# PIC_closed_loop.net
KiCad netlist of a schematic drawn in Altium Designer
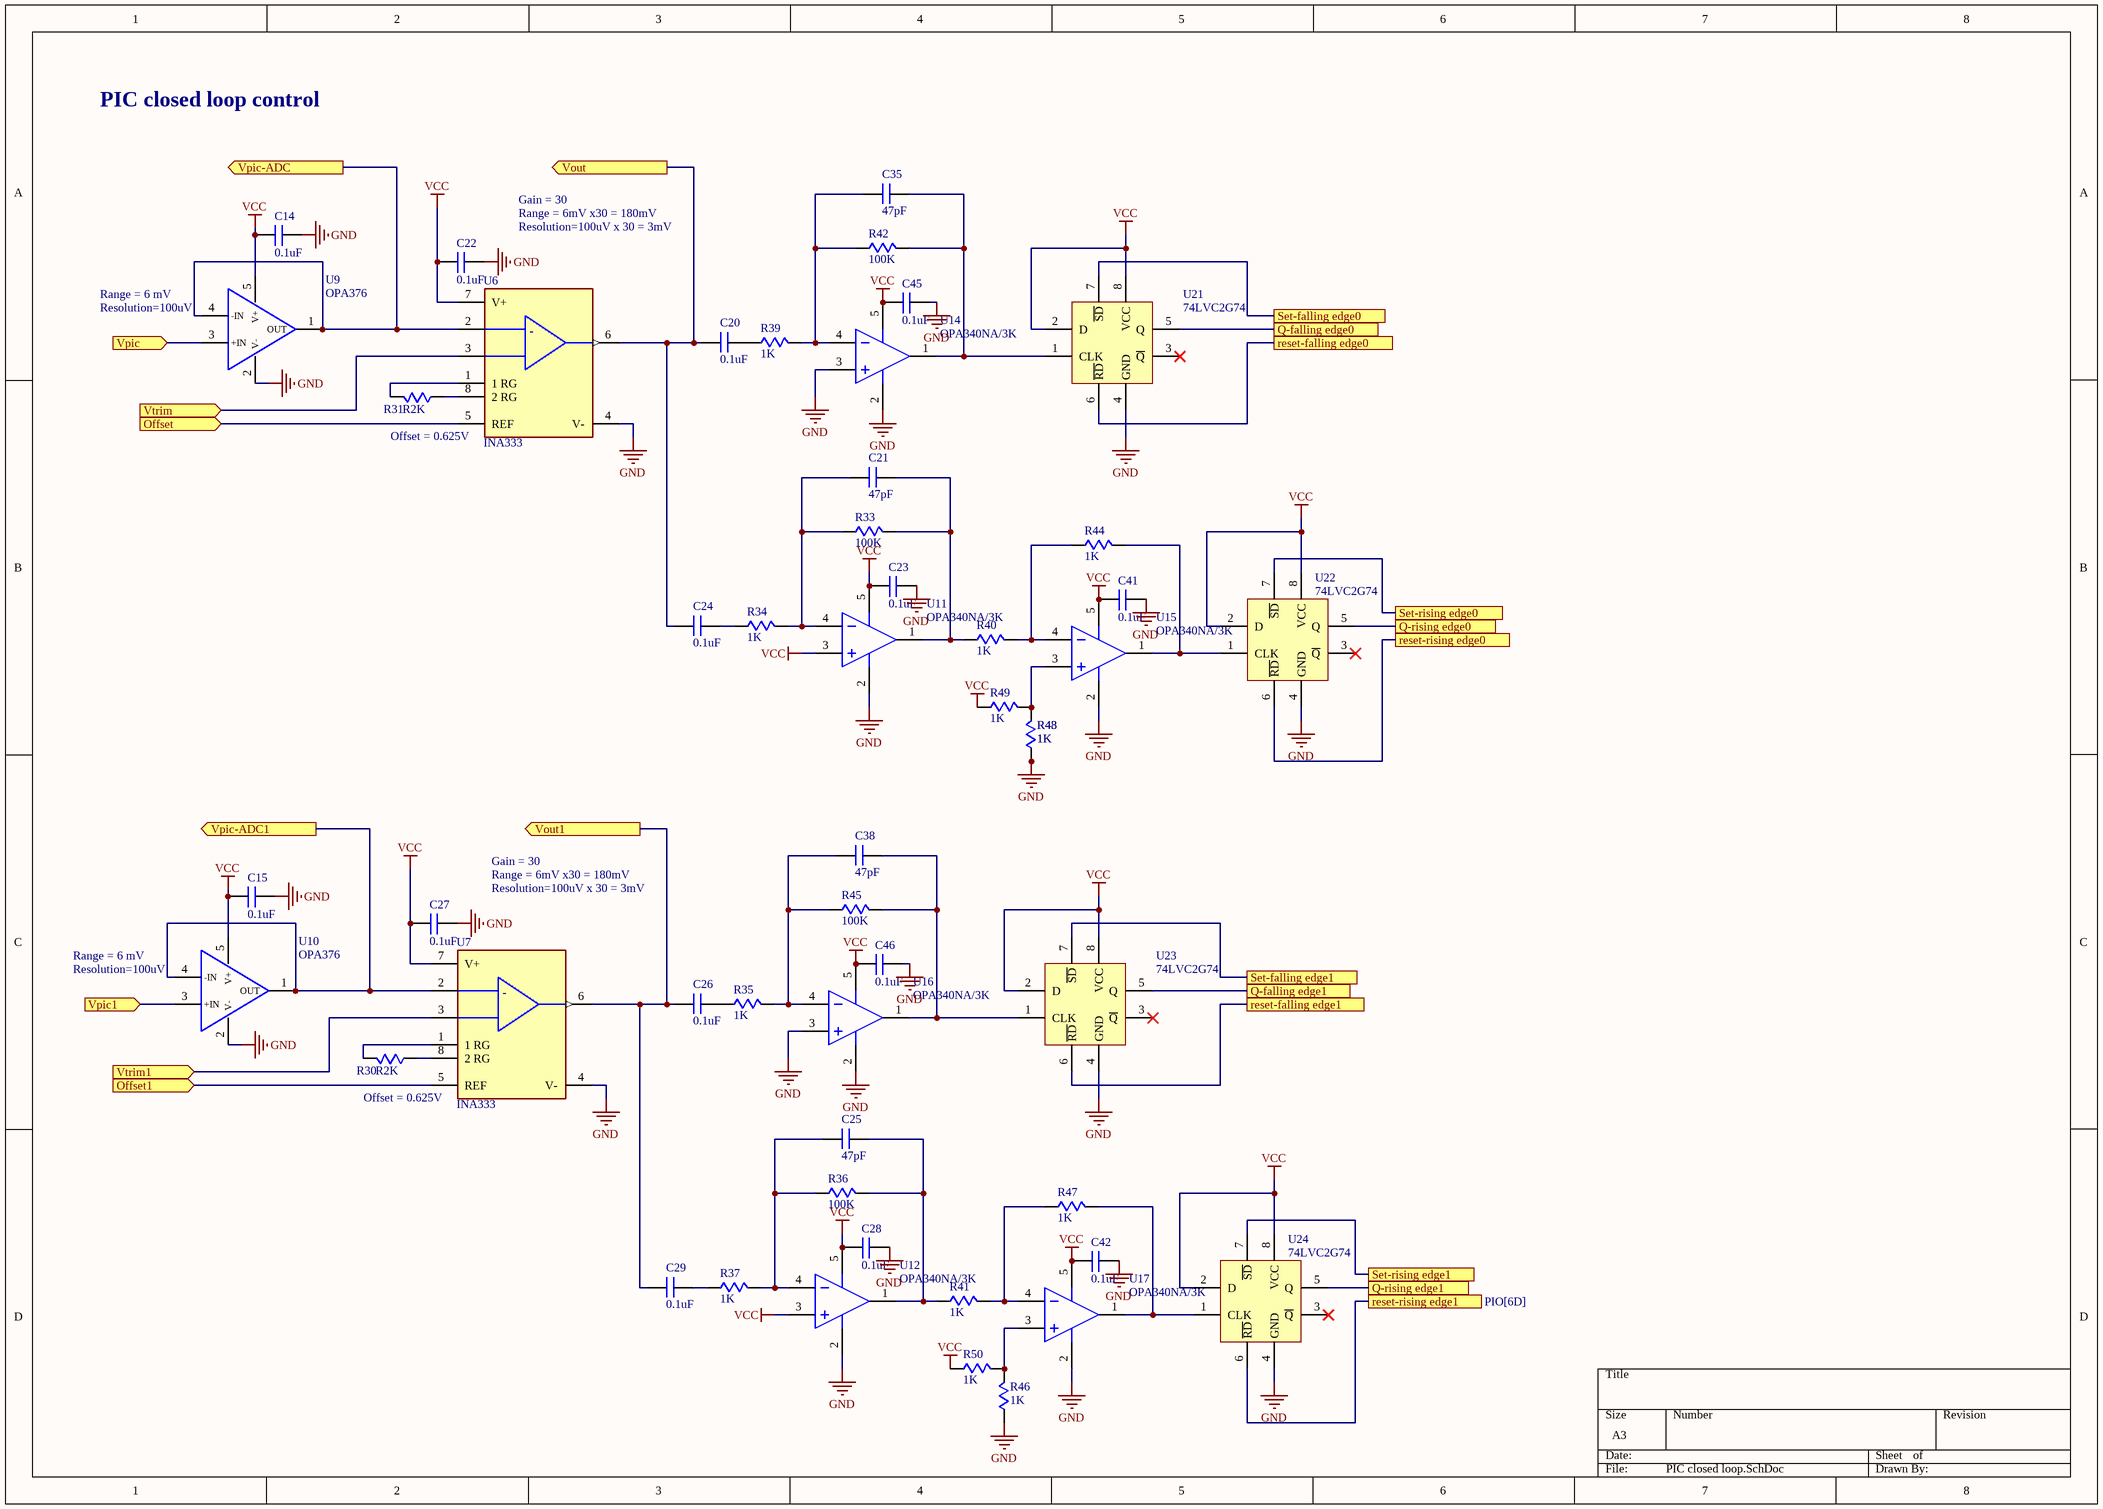
[diagram p0: PIC closed loop.SchDoc]

(export (version "E")
  (design (tool "Eeschema 10.0.6"))
  (components
    (comp (ref "C14")
      (value "0.1uF")
      (footprint "CAP0603")
      (description "50V 100nF X5R 卤10% 0603 Multilayer Ceramic Capacitors MLCC - SMD/SMT ROHS")
      (fields
        (field (name "MANUFACTURER") "TDK")
        (field (name "MANUFACTURER PART NUMBER") "C1608X5R1H104K080AA")
      )
      (libsource (lib "Pilot") (part "Capacitor 0.1uF"))
    )
    (comp (ref "C15")
      (value "0.1uF")
      (footprint "CAP0603")
      (description "50V 100nF X5R 卤10% 0603 Multilayer Ceramic Capacitors MLCC - SMD/SMT ROHS")
      (fields
        (field (name "MANUFACTURER") "TDK")
        (field (name "MANUFACTURER PART NUMBER") "C1608X5R1H104K080AA")
      )
      (libsource (lib "Pilot") (part "Capacitor 0.1uF"))
    )
    (comp (ref "C20")
      (value "0.1uF")
      (footprint "CAP0603")
      (description "50V 100nF X5R 卤10% 0603 Multilayer Ceramic Capacitors MLCC - SMD/SMT ROHS")
      (fields
        (field (name "MANUFACTURER") "TDK")
        (field (name "MANUFACTURER PART NUMBER") "C1608X5R1H104K080AA")
      )
      (libsource (lib "Pilot") (part "Capacitor 0.1uF"))
    )
    (comp (ref "C21")
      (value "47pF")
      (footprint "CAP0805")
      (description "Cap Cer 4.7PF 100V C0G/NP0 0805")
      (fields
        (field (name "MANUFACTURER") "Wurth Electronics")
        (field (name "MANUFACTURER PART NUMBER") "885012007096")
      )
      (libsource (lib "Pilot") (part "Capactior 47pF"))
    )
    (comp (ref "C22")
      (value "0.1uF")
      (footprint "CAP0603")
      (description "50V 100nF X5R 卤10% 0603 Multilayer Ceramic Capacitors MLCC - SMD/SMT ROHS")
      (fields
        (field (name "MANUFACTURER") "TDK")
        (field (name "MANUFACTURER PART NUMBER") "C1608X5R1H104K080AA")
      )
      (libsource (lib "Pilot") (part "Capacitor 0.1uF"))
    )
    (comp (ref "C23")
      (value "0.1uF")
      (footprint "CAP0603")
      (description "50V 100nF X5R 卤10% 0603 Multilayer Ceramic Capacitors MLCC - SMD/SMT ROHS")
      (fields
        (field (name "MANUFACTURER") "TDK")
        (field (name "MANUFACTURER PART NUMBER") "C1608X5R1H104K080AA")
      )
      (libsource (lib "Pilot") (part "Capacitor 0.1uF"))
    )
    (comp (ref "C24")
      (value "0.1uF")
      (footprint "CAP0603")
      (description "50V 100nF X5R 卤10% 0603 Multilayer Ceramic Capacitors MLCC - SMD/SMT ROHS")
      (fields
        (field (name "MANUFACTURER") "TDK")
        (field (name "MANUFACTURER PART NUMBER") "C1608X5R1H104K080AA")
      )
      (libsource (lib "Pilot") (part "Capacitor 0.1uF"))
    )
    (comp (ref "C25")
      (value "47pF")
      (footprint "CAP0805")
      (description "Cap Cer 4.7PF 100V C0G/NP0 0805")
      (fields
        (field (name "MANUFACTURER") "Wurth Electronics")
        (field (name "MANUFACTURER PART NUMBER") "885012007096")
      )
      (libsource (lib "Pilot") (part "Capactior 47pF"))
    )
    (comp (ref "C26")
      (value "0.1uF")
      (footprint "CAP0603")
      (description "50V 100nF X5R 卤10% 0603 Multilayer Ceramic Capacitors MLCC - SMD/SMT ROHS")
      (fields
        (field (name "MANUFACTURER") "TDK")
        (field (name "MANUFACTURER PART NUMBER") "C1608X5R1H104K080AA")
      )
      (libsource (lib "Pilot") (part "Capacitor 0.1uF"))
    )
    (comp (ref "C27")
      (value "0.1uF")
      (footprint "CAP0603")
      (description "50V 100nF X5R 卤10% 0603 Multilayer Ceramic Capacitors MLCC - SMD/SMT ROHS")
      (fields
        (field (name "MANUFACTURER") "TDK")
        (field (name "MANUFACTURER PART NUMBER") "C1608X5R1H104K080AA")
      )
      (libsource (lib "Pilot") (part "Capacitor 0.1uF"))
    )
    (comp (ref "C28")
      (value "0.1uF")
      (footprint "CAP0603")
      (description "50V 100nF X5R 卤10% 0603 Multilayer Ceramic Capacitors MLCC - SMD/SMT ROHS")
      (fields
        (field (name "MANUFACTURER") "TDK")
        (field (name "MANUFACTURER PART NUMBER") "C1608X5R1H104K080AA")
      )
      (libsource (lib "Pilot") (part "Capacitor 0.1uF"))
    )
    (comp (ref "C29")
      (value "0.1uF")
      (footprint "CAP0603")
      (description "50V 100nF X5R 卤10% 0603 Multilayer Ceramic Capacitors MLCC - SMD/SMT ROHS")
      (fields
        (field (name "MANUFACTURER") "TDK")
        (field (name "MANUFACTURER PART NUMBER") "C1608X5R1H104K080AA")
      )
      (libsource (lib "Pilot") (part "Capacitor 0.1uF"))
    )
    (comp (ref "C35")
      (value "47pF")
      (footprint "CAP0805")
      (description "Cap Cer 4.7PF 100V C0G/NP0 0805")
      (fields
        (field (name "MANUFACTURER") "Wurth Electronics")
        (field (name "MANUFACTURER PART NUMBER") "885012007096")
      )
      (libsource (lib "Pilot") (part "Capactior 47pF"))
    )
    (comp (ref "C38")
      (value "47pF")
      (footprint "CAP0805")
      (description "Cap Cer 4.7PF 100V C0G/NP0 0805")
      (fields
        (field (name "MANUFACTURER") "Wurth Electronics")
        (field (name "MANUFACTURER PART NUMBER") "885012007096")
      )
      (libsource (lib "Pilot") (part "Capactior 47pF"))
    )
    (comp (ref "C41")
      (value "0.1uF")
      (footprint "CAP0603")
      (description "50V 100nF X5R 卤10% 0603 Multilayer Ceramic Capacitors MLCC - SMD/SMT ROHS")
      (fields
        (field (name "MANUFACTURER") "TDK")
        (field (name "MANUFACTURER PART NUMBER") "C1608X5R1H104K080AA")
      )
      (libsource (lib "Pilot") (part "Capacitor 0.1uF"))
    )
    (comp (ref "C42")
      (value "0.1uF")
      (footprint "CAP0603")
      (description "50V 100nF X5R 卤10% 0603 Multilayer Ceramic Capacitors MLCC - SMD/SMT ROHS")
      (fields
        (field (name "MANUFACTURER") "TDK")
        (field (name "MANUFACTURER PART NUMBER") "C1608X5R1H104K080AA")
      )
      (libsource (lib "Pilot") (part "Capacitor 0.1uF"))
    )
    (comp (ref "C45")
      (value "0.1uF")
      (footprint "CAP0603")
      (description "50V 100nF X5R 卤10% 0603 Multilayer Ceramic Capacitors MLCC - SMD/SMT ROHS")
      (fields
        (field (name "MANUFACTURER") "TDK")
        (field (name "MANUFACTURER PART NUMBER") "C1608X5R1H104K080AA")
      )
      (libsource (lib "Pilot") (part "Capacitor 0.1uF"))
    )
    (comp (ref "C46")
      (value "0.1uF")
      (footprint "CAP0603")
      (description "50V 100nF X5R 卤10% 0603 Multilayer Ceramic Capacitors MLCC - SMD/SMT ROHS")
      (fields
        (field (name "MANUFACTURER") "TDK")
        (field (name "MANUFACTURER PART NUMBER") "C1608X5R1H104K080AA")
      )
      (libsource (lib "Pilot") (part "Capacitor 0.1uF"))
    )
    (comp (ref "R30")
      (value "R2K")
      (footprint "RES0603")
      (description "Res Thin Film 0603 2K Ohm 0.1% 1/10W ±25ppm/°C Molded SMD SMD Paper T/R")
      (fields
        (field (name "MANUFACTURER") "Yageo")
        (field (name "MANUFACTURER PART NUMBER") "RT0603BRD072KL")
      )
      (libsource (lib "Pilot") (part "Resistor 2K"))
    )
    (comp (ref "R31")
      (value "R2K")
      (footprint "RES0603")
      (description "Res Thin Film 0603 2K Ohm 0.1% 1/10W ±25ppm/°C Molded SMD SMD Paper T/R")
      (fields
        (field (name "MANUFACTURER") "Yageo")
        (field (name "MANUFACTURER PART NUMBER") "RT0603BRD072KL")
      )
      (libsource (lib "Pilot") (part "Resistor 2K"))
    )
    (comp (ref "R33")
      (value "100K")
      (footprint "RES0805")
      (description "Res Thick Film 0805 100K Ohm 5% 0.125W(1/8W) +/-200ppm/ßC SMD Automotive T/R")
      (fields
        (field (name "MANUFACTURER") "Panasonic")
        (field (name "MANUFACTURER PART NUMBER") "ERJ-6GEYJ104V")
      )
      (libsource (lib "Pilot") (part "Resistor 100K"))
    )
    (comp (ref "R34") (value "1K") (footprint "RES0805") (libsource (lib "Pilot") (part "Resistor 1K")))
    (comp (ref "R35") (value "1K") (footprint "RES0805") (libsource (lib "Pilot") (part "Resistor 1K")))
    (comp (ref "R36")
      (value "100K")
      (footprint "RES0805")
      (description "Res Thick Film 0805 100K Ohm 5% 0.125W(1/8W) +/-200ppm/ßC SMD Automotive T/R")
      (fields
        (field (name "MANUFACTURER") "Panasonic")
        (field (name "MANUFACTURER PART NUMBER") "ERJ-6GEYJ104V")
      )
      (libsource (lib "Pilot") (part "Resistor 100K"))
    )
    (comp (ref "R37") (value "1K") (footprint "RES0805") (libsource (lib "Pilot") (part "Resistor 1K")))
    (comp (ref "R39") (value "1K") (footprint "RES0805") (libsource (lib "Pilot") (part "Resistor 1K")))
    (comp (ref "R40") (value "1K") (footprint "RES0805") (libsource (lib "Pilot") (part "Resistor 1K")))
    (comp (ref "R41") (value "1K") (footprint "RES0805") (libsource (lib "Pilot") (part "Resistor 1K")))
    (comp (ref "R42")
      (value "100K")
      (footprint "RES0805")
      (description "Res Thick Film 0805 100K Ohm 5% 0.125W(1/8W) +/-200ppm/ßC SMD Automotive T/R")
      (fields
        (field (name "MANUFACTURER") "Panasonic")
        (field (name "MANUFACTURER PART NUMBER") "ERJ-6GEYJ104V")
      )
      (libsource (lib "Pilot") (part "Resistor 100K"))
    )
    (comp (ref "R43") (value "1K") (footprint "RES0805") (libsource (lib "Pilot") (part "Resistor 1K")))
    (comp (ref "R44") (value "1K") (footprint "RES0805") (libsource (lib "Pilot") (part "Resistor 1K")))
    (comp (ref "R45")
      (value "100K")
      (footprint "RES0805")
      (description "Res Thick Film 0805 100K Ohm 5% 0.125W(1/8W) +/-200ppm/ßC SMD Automotive T/R")
      (fields
        (field (name "MANUFACTURER") "Panasonic")
        (field (name "MANUFACTURER PART NUMBER") "ERJ-6GEYJ104V")
      )
      (libsource (lib "Pilot") (part "Resistor 100K"))
    )
    (comp (ref "R46") (value "1K") (footprint "RES0805") (libsource (lib "Pilot") (part "Resistor 1K")))
    (comp (ref "R47") (value "1K") (footprint "RES0805") (libsource (lib "Pilot") (part "Resistor 1K")))
    (comp (ref "R48") (value "1K") (footprint "RES0805") (libsource (lib "Pilot") (part "Resistor 1K")))
    (comp (ref "R49") (value "1K") (footprint "RES0805") (libsource (lib "Pilot") (part "Resistor 1K")))
    (comp (ref "R50") (value "1K") (footprint "RES0805") (libsource (lib "Pilot") (part "Resistor 1K")))
    (comp (ref "U6")
      (value "INA333")
      (footprint "VSSOP-8")
      (description "IC INST AMP 1 CIRCUIT 8VSSOP Instrumentation Amplifier 1 Circuit Rail-to-Rail 8-VSSOP")
      (fields
        (field (name "MANUFACTURER") "Texas Instruments")
        (field (name "MANUFACTURER PART NUMBER") "INA333AIDGKT")
      )
      (libsource (lib "Pilot") (part "INA333AIDGKT"))
    )
    (comp (ref "U7")
      (value "INA333")
      (footprint "VSSOP-8")
      (description "IC INST AMP 1 CIRCUIT 8VSSOP Instrumentation Amplifier 1 Circuit Rail-to-Rail 8-VSSOP")
      (fields
        (field (name "MANUFACTURER") "Texas Instruments")
        (field (name "MANUFACTURER PART NUMBER") "INA333AIDGKT")
      )
      (libsource (lib "Pilot") (part "INA333AIDGKT"))
    )
    (comp (ref "U9")
      (value "OPA376")
      (footprint "SOT-23-5")
      (description "Automotive Precision, Low Noise, Low Iq Operational Amplifier 5-SOT-23 -40 to 125")
      (fields
        (field (name "MANUFACTURER") "Texas Instruments")
        (field (name "MANUFACTURER PART NUMBER") "OPA376AQDBVRQ1")
      )
      (libsource (lib "Pilot") (part "OPA376"))
    )
    (comp (ref "U10")
      (value "OPA376")
      (footprint "SOT-23-5")
      (description "Automotive Precision, Low Noise, Low Iq Operational Amplifier 5-SOT-23 -40 to 125")
      (fields
        (field (name "MANUFACTURER") "Texas Instruments")
        (field (name "MANUFACTURER PART NUMBER") "OPA376AQDBVRQ1")
      )
      (libsource (lib "Pilot") (part "OPA376"))
    )
    (comp (ref "U11")
      (value "OPA340NA/3K")
      (footprint "SOT-23")
      (description "Operational Amplifier Single General Purpose Rail to Rail Input 5.5V 5-Pin SOT-23 Tape and Reel")
      (fields (field (name "MANUFACTURER") "Texas Instruments"))
      (libsource (lib "Pilot") (part "OPA340"))
    )
    (comp (ref "U12")
      (value "OPA340NA/3K")
      (footprint "SOT-23")
      (description "Operational Amplifier Single General Purpose Rail to Rail Input 5.5V 5-Pin SOT-23 Tape and Reel")
      (fields (field (name "MANUFACTURER") "Texas Instruments"))
      (libsource (lib "Pilot") (part "OPA340"))
    )
    (comp (ref "U14")
      (value "OPA340NA/3K")
      (footprint "SOT-23")
      (description "Operational Amplifier Single General Purpose Rail to Rail Input 5.5V 5-Pin SOT-23 Tape and Reel")
      (fields (field (name "MANUFACTURER") "Texas Instruments"))
      (libsource (lib "Pilot") (part "OPA340"))
    )
    (comp (ref "U15")
      (value "OPA340NA/3K")
      (footprint "SOT-23")
      (description "Operational Amplifier Single General Purpose Rail to Rail Input 5.5V 5-Pin SOT-23 Tape and Reel")
      (fields (field (name "MANUFACTURER") "Texas Instruments"))
      (libsource (lib "Pilot") (part "OPA340"))
    )
    (comp (ref "U16")
      (value "OPA340NA/3K")
      (footprint "SOT-23")
      (description "Operational Amplifier Single General Purpose Rail to Rail Input 5.5V 5-Pin SOT-23 Tape and Reel")
      (fields (field (name "MANUFACTURER") "Texas Instruments"))
      (libsource (lib "Pilot") (part "OPA340"))
    )
    (comp (ref "U17")
      (value "OPA340NA/3K")
      (footprint "SOT-23")
      (description "Operational Amplifier Single General Purpose Rail to Rail Input 5.5V 5-Pin SOT-23 Tape and Reel")
      (fields (field (name "MANUFACTURER") "Texas Instruments"))
      (libsource (lib "Pilot") (part "OPA340"))
    )
    (comp (ref "U21")
      (value "74LVC2G74")
      (footprint "TSSOP8")
      (description "Flip-Flop with Set And Reset Single D-Type Positive Edge Trigger 1.65V to 5.5V 8-Pin TSSOP")
      (fields
        (field (name "MANUFACTURER") "Nexperia")
        (field (name "MANUFACTURER PART NUMBER") "74LVC2G74DP,125")
      )
      (libsource (lib "Pilot") (part "74LVC2G74DP,125"))
    )
    (comp (ref "U22")
      (value "74LVC2G74")
      (footprint "TSSOP8")
      (description "Flip-Flop with Set And Reset Single D-Type Positive Edge Trigger 1.65V to 5.5V 8-Pin TSSOP")
      (fields
        (field (name "MANUFACTURER") "Nexperia")
        (field (name "MANUFACTURER PART NUMBER") "74LVC2G74DP,125")
      )
      (libsource (lib "Pilot") (part "74LVC2G74DP,125"))
    )
    (comp (ref "U23")
      (value "74LVC2G74")
      (footprint "TSSOP8")
      (description "Flip-Flop with Set And Reset Single D-Type Positive Edge Trigger 1.65V to 5.5V 8-Pin TSSOP")
      (fields
        (field (name "MANUFACTURER") "Nexperia")
        (field (name "MANUFACTURER PART NUMBER") "74LVC2G74DP,125")
      )
      (libsource (lib "Pilot") (part "74LVC2G74DP,125"))
    )
    (comp (ref "U24")
      (value "74LVC2G74")
      (footprint "TSSOP8")
      (description "Flip-Flop with Set And Reset Single D-Type Positive Edge Trigger 1.65V to 5.5V 8-Pin TSSOP")
      (fields
        (field (name "MANUFACTURER") "Nexperia")
        (field (name "MANUFACTURER PART NUMBER") "74LVC2G74DP,125")
      )
      (libsource (lib "Pilot") (part "74LVC2G74DP,125"))
    )
  )
  (nets
    (net (code "1") (name "/Offset") (class "Default")
      (node (ref "U6") (pin "5") (pinfunction "REF_5") (pintype "passive"))
    )
    (net (code "2") (name "/Offset1") (class "Default")
      (node (ref "U7") (pin "5") (pinfunction "REF_5") (pintype "passive"))
    )
    (net (code "3") (name "/Q-falling edge0") (class "Default")
      (node (ref "U21") (pin "5") (pinfunction "Q_5") (pintype "passive"))
    )
    (net (code "4") (name "/Q-falling edge1") (class "Default")
      (node (ref "U23") (pin "5") (pinfunction "Q_5") (pintype "passive"))
    )
    (net (code "5") (name "/Q-rising edge0") (class "Default")
      (node (ref "U22") (pin "5") (pinfunction "Q_5") (pintype "passive"))
    )
    (net (code "6") (name "/Q-rising edge1") (class "Default")
      (node (ref "U24") (pin "5") (pinfunction "Q_5") (pintype "passive"))
    )
    (net (code "7") (name "/Set-falling edge0") (class "Default")
      (node (ref "U21") (pin "7") (pinfunction "~{SD}_7") (pintype "passive"))
    )
    (net (code "8") (name "/Set-falling edge1") (class "Default")
      (node (ref "U23") (pin "7") (pinfunction "~{SD}_7") (pintype "passive"))
    )
    (net (code "9") (name "/Set-rising edge0") (class "Default")
      (node (ref "U22") (pin "7") (pinfunction "~{SD}_7") (pintype "passive"))
    )
    (net (code "10") (name "/Set-rising edge1") (class "Default")
      (node (ref "U24") (pin "7") (pinfunction "~{SD}_7") (pintype "passive"))
    )
    (net (code "11") (name "/Vout") (class "Default")
      (node (ref "C20") (pin "1") (pinfunction "1_1") (pintype "passive"))
      (node (ref "C24") (pin "1") (pinfunction "1_1") (pintype "passive"))
      (node (ref "U6") (pin "6") (pinfunction "VOUT_6") (pintype "output"))
    )
    (net (code "12") (name "/Vout1") (class "Default")
      (node (ref "C26") (pin "1") (pinfunction "1_1") (pintype "passive"))
      (node (ref "C29") (pin "1") (pinfunction "1_1") (pintype "passive"))
      (node (ref "U7") (pin "6") (pinfunction "VOUT_6") (pintype "output"))
    )
    (net (code "13") (name "/Vpic") (class "Default")
      (node (ref "U9") (pin "3") (pinfunction "+IN_3") (pintype "passive"))
    )
    (net (code "14") (name "/Vpic-ADC") (class "Default")
      (node (ref "U6") (pin "2") (pinfunction "VIN-_2") (pintype "passive"))
      (node (ref "U9") (pin "1") (pinfunction "OUT_1") (pintype "passive"))
      (node (ref "U9") (pin "4") (pinfunction "-IN_4") (pintype "passive"))
    )
    (net (code "15") (name "/Vpic-ADC1") (class "Default")
      (node (ref "U10") (pin "1") (pinfunction "OUT_1") (pintype "passive"))
      (node (ref "U10") (pin "4") (pinfunction "-IN_4") (pintype "passive"))
      (node (ref "U7") (pin "2") (pinfunction "VIN-_2") (pintype "passive"))
    )
    (net (code "16") (name "/Vpic1") (class "Default")
      (node (ref "U10") (pin "3") (pinfunction "+IN_3") (pintype "passive"))
    )
    (net (code "17") (name "/Vtrim") (class "Default")
      (node (ref "U6") (pin "3") (pinfunction "VIN+_3") (pintype "passive"))
    )
    (net (code "18") (name "/Vtrim1") (class "Default")
      (node (ref "U7") (pin "3") (pinfunction "VIN+_3") (pintype "passive"))
    )
    (net (code "19") (name "/reset-falling edge0") (class "Default")
      (node (ref "U21") (pin "6") (pinfunction "~{RD}_6") (pintype "passive"))
    )
    (net (code "20") (name "/reset-falling edge1") (class "Default")
      (node (ref "U23") (pin "6") (pinfunction "~{RD}_6") (pintype "passive"))
    )
    (net (code "21") (name "/reset-rising edge0") (class "Default")
      (node (ref "U22") (pin "6") (pinfunction "~{RD}_6") (pintype "passive"))
    )
    (net (code "22") (name "/reset-rising edge1") (class "Default")
      (node (ref "U24") (pin "6") (pinfunction "~{RD}_6") (pintype "passive"))
    )
    (net (code "23") (name "GND") (class "Default")
      (node (ref "C14") (pin "1") (pinfunction "1_1") (pintype "passive"))
      (node (ref "C15") (pin "1") (pinfunction "1_1") (pintype "passive"))
      (node (ref "C22") (pin "1") (pinfunction "1_1") (pintype "passive"))
      (node (ref "C23") (pin "1") (pinfunction "1_1") (pintype "passive"))
      (node (ref "C27") (pin "1") (pinfunction "1_1") (pintype "passive"))
      (node (ref "C28") (pin "1") (pinfunction "1_1") (pintype "passive"))
      (node (ref "C41") (pin "1") (pinfunction "1_1") (pintype "passive"))
      (node (ref "C42") (pin "1") (pinfunction "1_1") (pintype "passive"))
      (node (ref "C45") (pin "1") (pinfunction "1_1") (pintype "passive"))
      (node (ref "C46") (pin "1") (pinfunction "1_1") (pintype "passive"))
      (node (ref "R43") (pin "1") (pinfunction "1_1") (pintype "passive"))
      (node (ref "R46") (pin "1") (pinfunction "1_1") (pintype "passive"))
      (node (ref "R48") (pin "1") (pinfunction "1_1") (pintype "passive"))
      (node (ref "U10") (pin "2") (pinfunction "V-_2") (pintype "passive"))
      (node (ref "U11") (pin "2") (pinfunction "V-_2") (pintype "power_in"))
      (node (ref "U12") (pin "2") (pinfunction "V-_2") (pintype "power_in"))
      (node (ref "U14") (pin "2") (pinfunction "V-_2") (pintype "power_in"))
      (node (ref "U14") (pin "3") (pinfunction "IN+_3") (pintype "passive"))
      (node (ref "U15") (pin "2") (pinfunction "V-_2") (pintype "power_in"))
      (node (ref "U16") (pin "2") (pinfunction "V-_2") (pintype "power_in"))
      (node (ref "U16") (pin "3") (pinfunction "IN+_3") (pintype "passive"))
      (node (ref "U17") (pin "2") (pinfunction "V-_2") (pintype "power_in"))
      (node (ref "U21") (pin "4") (pinfunction "GND_4") (pintype "passive"))
      (node (ref "U22") (pin "4") (pinfunction "GND_4") (pintype "passive"))
      (node (ref "U23") (pin "4") (pinfunction "GND_4") (pintype "passive"))
      (node (ref "U24") (pin "4") (pinfunction "GND_4") (pintype "passive"))
      (node (ref "U6") (pin "4") (pinfunction "V-_4") (pintype "power_in"))
      (node (ref "U7") (pin "4") (pinfunction "V-_4") (pintype "power_in"))
      (node (ref "U9") (pin "2") (pinfunction "V-_2") (pintype "passive"))
    )
    (net (code "24") (name "Net-(C20-Pad2)") (class "Default")
      (node (ref "C20") (pin "2") (pinfunction "2_2") (pintype "passive"))
      (node (ref "R39") (pin "1") (pinfunction "1_1") (pintype "passive"))
    )
    (net (code "25") (name "Net-(C24-Pad2)") (class "Default")
      (node (ref "C24") (pin "2") (pinfunction "2_2") (pintype "passive"))
      (node (ref "R34") (pin "1") (pinfunction "1_1") (pintype "passive"))
    )
    (net (code "26") (name "Net-(C26-Pad2)") (class "Default")
      (node (ref "C26") (pin "2") (pinfunction "2_2") (pintype "passive"))
      (node (ref "R35") (pin "1") (pinfunction "1_1") (pintype "passive"))
    )
    (net (code "27") (name "Net-(C29-Pad2)") (class "Default")
      (node (ref "C29") (pin "2") (pinfunction "2_2") (pintype "passive"))
      (node (ref "R37") (pin "1") (pinfunction "1_1") (pintype "passive"))
    )
    (net (code "28") (name "Net-(U6-1_RG)") (class "Default")
      (node (ref "R31") (pin "2") (pinfunction "2_2") (pintype "passive"))
      (node (ref "U6") (pin "1") (pinfunction "1_RG_1") (pintype "passive"))
    )
    (net (code "29") (name "Net-(U6-2_RG)") (class "Default")
      (node (ref "R31") (pin "1") (pinfunction "1_1") (pintype "passive"))
      (node (ref "U6") (pin "8") (pinfunction "2_RG_8") (pintype "passive"))
    )
    (net (code "30") (name "Net-(U7-1_RG)") (class "Default")
      (node (ref "R30") (pin "2") (pinfunction "2_2") (pintype "passive"))
      (node (ref "U7") (pin "1") (pinfunction "1_RG_1") (pintype "passive"))
    )
    (net (code "31") (name "Net-(U7-2_RG)") (class "Default")
      (node (ref "R30") (pin "1") (pinfunction "1_1") (pintype "passive"))
      (node (ref "U7") (pin "8") (pinfunction "2_RG_8") (pintype "passive"))
    )
    (net (code "32") (name "Net-(U11-IN-)") (class "Default")
      (node (ref "C21") (pin "1") (pinfunction "1_1") (pintype "passive"))
      (node (ref "R33") (pin "1") (pinfunction "1_1") (pintype "passive"))
      (node (ref "R34") (pin "2") (pinfunction "2_2") (pintype "passive"))
      (node (ref "U11") (pin "4") (pinfunction "IN-_4") (pintype "passive"))
    )
    (net (code "33") (name "Net-(U11-OUT)") (class "Default")
      (node (ref "C21") (pin "2") (pinfunction "2_2") (pintype "passive"))
      (node (ref "R33") (pin "2") (pinfunction "2_2") (pintype "passive"))
      (node (ref "R40") (pin "1") (pinfunction "1_1") (pintype "passive"))
      (node (ref "U11") (pin "1") (pinfunction "OUT_1") (pintype "passive"))
    )
    (net (code "34") (name "Net-(U12-IN-)") (class "Default")
      (node (ref "C25") (pin "1") (pinfunction "1_1") (pintype "passive"))
      (node (ref "R36") (pin "1") (pinfunction "1_1") (pintype "passive"))
      (node (ref "R37") (pin "2") (pinfunction "2_2") (pintype "passive"))
      (node (ref "U12") (pin "4") (pinfunction "IN-_4") (pintype "passive"))
    )
    (net (code "35") (name "Net-(U12-OUT)") (class "Default")
      (node (ref "C25") (pin "2") (pinfunction "2_2") (pintype "passive"))
      (node (ref "R36") (pin "2") (pinfunction "2_2") (pintype "passive"))
      (node (ref "R41") (pin "1") (pinfunction "1_1") (pintype "passive"))
      (node (ref "U12") (pin "1") (pinfunction "OUT_1") (pintype "passive"))
    )
    (net (code "36") (name "Net-(U14-IN-)") (class "Default")
      (node (ref "C35") (pin "1") (pinfunction "1_1") (pintype "passive"))
      (node (ref "R39") (pin "2") (pinfunction "2_2") (pintype "passive"))
      (node (ref "R42") (pin "1") (pinfunction "1_1") (pintype "passive"))
      (node (ref "U14") (pin "4") (pinfunction "IN-_4") (pintype "passive"))
    )
    (net (code "37") (name "Net-(U14-OUT)") (class "Default")
      (node (ref "C35") (pin "2") (pinfunction "2_2") (pintype "passive"))
      (node (ref "R42") (pin "2") (pinfunction "2_2") (pintype "passive"))
      (node (ref "U14") (pin "1") (pinfunction "OUT_1") (pintype "passive"))
      (node (ref "U21") (pin "1") (pinfunction "CLK_1") (pintype "passive"))
    )
    (net (code "38") (name "Net-(U15-IN+)") (class "Default")
      (node (ref "R43") (pin "2") (pinfunction "2_2") (pintype "passive"))
      (node (ref "R48") (pin "2") (pinfunction "2_2") (pintype "passive"))
      (node (ref "R49") (pin "2") (pinfunction "2_2") (pintype "passive"))
      (node (ref "U15") (pin "3") (pinfunction "IN+_3") (pintype "passive"))
    )
    (net (code "39") (name "Net-(U15-IN-)") (class "Default")
      (node (ref "R40") (pin "2") (pinfunction "2_2") (pintype "passive"))
      (node (ref "R44") (pin "1") (pinfunction "1_1") (pintype "passive"))
      (node (ref "U15") (pin "4") (pinfunction "IN-_4") (pintype "passive"))
    )
    (net (code "40") (name "Net-(U15-OUT)") (class "Default")
      (node (ref "R44") (pin "2") (pinfunction "2_2") (pintype "passive"))
      (node (ref "U15") (pin "1") (pinfunction "OUT_1") (pintype "passive"))
      (node (ref "U22") (pin "1") (pinfunction "CLK_1") (pintype "passive"))
    )
    (net (code "41") (name "Net-(U16-IN-)") (class "Default")
      (node (ref "C38") (pin "1") (pinfunction "1_1") (pintype "passive"))
      (node (ref "R35") (pin "2") (pinfunction "2_2") (pintype "passive"))
      (node (ref "R45") (pin "1") (pinfunction "1_1") (pintype "passive"))
      (node (ref "U16") (pin "4") (pinfunction "IN-_4") (pintype "passive"))
    )
    (net (code "42") (name "Net-(U16-OUT)") (class "Default")
      (node (ref "C38") (pin "2") (pinfunction "2_2") (pintype "passive"))
      (node (ref "R45") (pin "2") (pinfunction "2_2") (pintype "passive"))
      (node (ref "U16") (pin "1") (pinfunction "OUT_1") (pintype "passive"))
      (node (ref "U23") (pin "1") (pinfunction "CLK_1") (pintype "passive"))
    )
    (net (code "43") (name "Net-(U17-IN+)") (class "Default")
      (node (ref "R46") (pin "2") (pinfunction "2_2") (pintype "passive"))
      (node (ref "R50") (pin "2") (pinfunction "2_2") (pintype "passive"))
      (node (ref "U17") (pin "3") (pinfunction "IN+_3") (pintype "passive"))
    )
    (net (code "44") (name "Net-(U17-IN-)") (class "Default")
      (node (ref "R41") (pin "2") (pinfunction "2_2") (pintype "passive"))
      (node (ref "R47") (pin "1") (pinfunction "1_1") (pintype "passive"))
      (node (ref "U17") (pin "4") (pinfunction "IN-_4") (pintype "passive"))
    )
    (net (code "45") (name "Net-(U17-OUT)") (class "Default")
      (node (ref "R47") (pin "2") (pinfunction "2_2") (pintype "passive"))
      (node (ref "U17") (pin "1") (pinfunction "OUT_1") (pintype "passive"))
      (node (ref "U24") (pin "1") (pinfunction "CLK_1") (pintype "passive"))
    )
    (net (code "46") (name "VCC") (class "Default")
      (node (ref "C14") (pin "2") (pinfunction "2_2") (pintype "passive"))
      (node (ref "C15") (pin "2") (pinfunction "2_2") (pintype "passive"))
      (node (ref "C22") (pin "2") (pinfunction "2_2") (pintype "passive"))
      (node (ref "C23") (pin "2") (pinfunction "2_2") (pintype "passive"))
      (node (ref "C27") (pin "2") (pinfunction "2_2") (pintype "passive"))
      (node (ref "C28") (pin "2") (pinfunction "2_2") (pintype "passive"))
      (node (ref "C41") (pin "2") (pinfunction "2_2") (pintype "passive"))
      (node (ref "C42") (pin "2") (pinfunction "2_2") (pintype "passive"))
      (node (ref "C45") (pin "2") (pinfunction "2_2") (pintype "passive"))
      (node (ref "C46") (pin "2") (pinfunction "2_2") (pintype "passive"))
      (node (ref "R49") (pin "1") (pinfunction "1_1") (pintype "passive"))
      (node (ref "R50") (pin "1") (pinfunction "1_1") (pintype "passive"))
      (node (ref "U10") (pin "5") (pinfunction "V+_5") (pintype "passive"))
      (node (ref "U11") (pin "3") (pinfunction "IN+_3") (pintype "passive"))
      (node (ref "U11") (pin "5") (pinfunction "V+_5") (pintype "power_in"))
      (node (ref "U12") (pin "3") (pinfunction "IN+_3") (pintype "passive"))
      (node (ref "U12") (pin "5") (pinfunction "V+_5") (pintype "power_in"))
      (node (ref "U14") (pin "5") (pinfunction "V+_5") (pintype "power_in"))
      (node (ref "U15") (pin "5") (pinfunction "V+_5") (pintype "power_in"))
      (node (ref "U16") (pin "5") (pinfunction "V+_5") (pintype "power_in"))
      (node (ref "U17") (pin "5") (pinfunction "V+_5") (pintype "power_in"))
      (node (ref "U21") (pin "2") (pinfunction "D_2") (pintype "passive"))
      (node (ref "U21") (pin "8") (pinfunction "VCC_8") (pintype "passive"))
      (node (ref "U22") (pin "2") (pinfunction "D_2") (pintype "passive"))
      (node (ref "U22") (pin "8") (pinfunction "VCC_8") (pintype "passive"))
      (node (ref "U23") (pin "2") (pinfunction "D_2") (pintype "passive"))
      (node (ref "U23") (pin "8") (pinfunction "VCC_8") (pintype "passive"))
      (node (ref "U24") (pin "2") (pinfunction "D_2") (pintype "passive"))
      (node (ref "U24") (pin "8") (pinfunction "VCC_8") (pintype "passive"))
      (node (ref "U6") (pin "7") (pinfunction "V+_7") (pintype "power_in"))
      (node (ref "U7") (pin "7") (pinfunction "V+_7") (pintype "power_in"))
      (node (ref "U9") (pin "5") (pinfunction "V+_5") (pintype "passive"))
    )
    (net (code "47") (name "unconnected-(U21-~{Q}-Pad3)") (class "Default")
      (node (ref "U21") (pin "3") (pinfunction "~{Q}_3") (pintype "passive+no_connect"))
    )
    (net (code "48") (name "unconnected-(U22-~{Q}-Pad3)") (class "Default")
      (node (ref "U22") (pin "3") (pinfunction "~{Q}_3") (pintype "passive+no_connect"))
    )
    (net (code "49") (name "unconnected-(U23-~{Q}-Pad3)") (class "Default")
      (node (ref "U23") (pin "3") (pinfunction "~{Q}_3") (pintype "passive+no_connect"))
    )
    (net (code "50") (name "unconnected-(U24-~{Q}-Pad3)") (class "Default")
      (node (ref "U24") (pin "3") (pinfunction "~{Q}_3") (pintype "passive+no_connect"))
    )
  )
)
